# p1_bt_sorry.net
KiCad netlist of a schematic drawn in Altium Designer
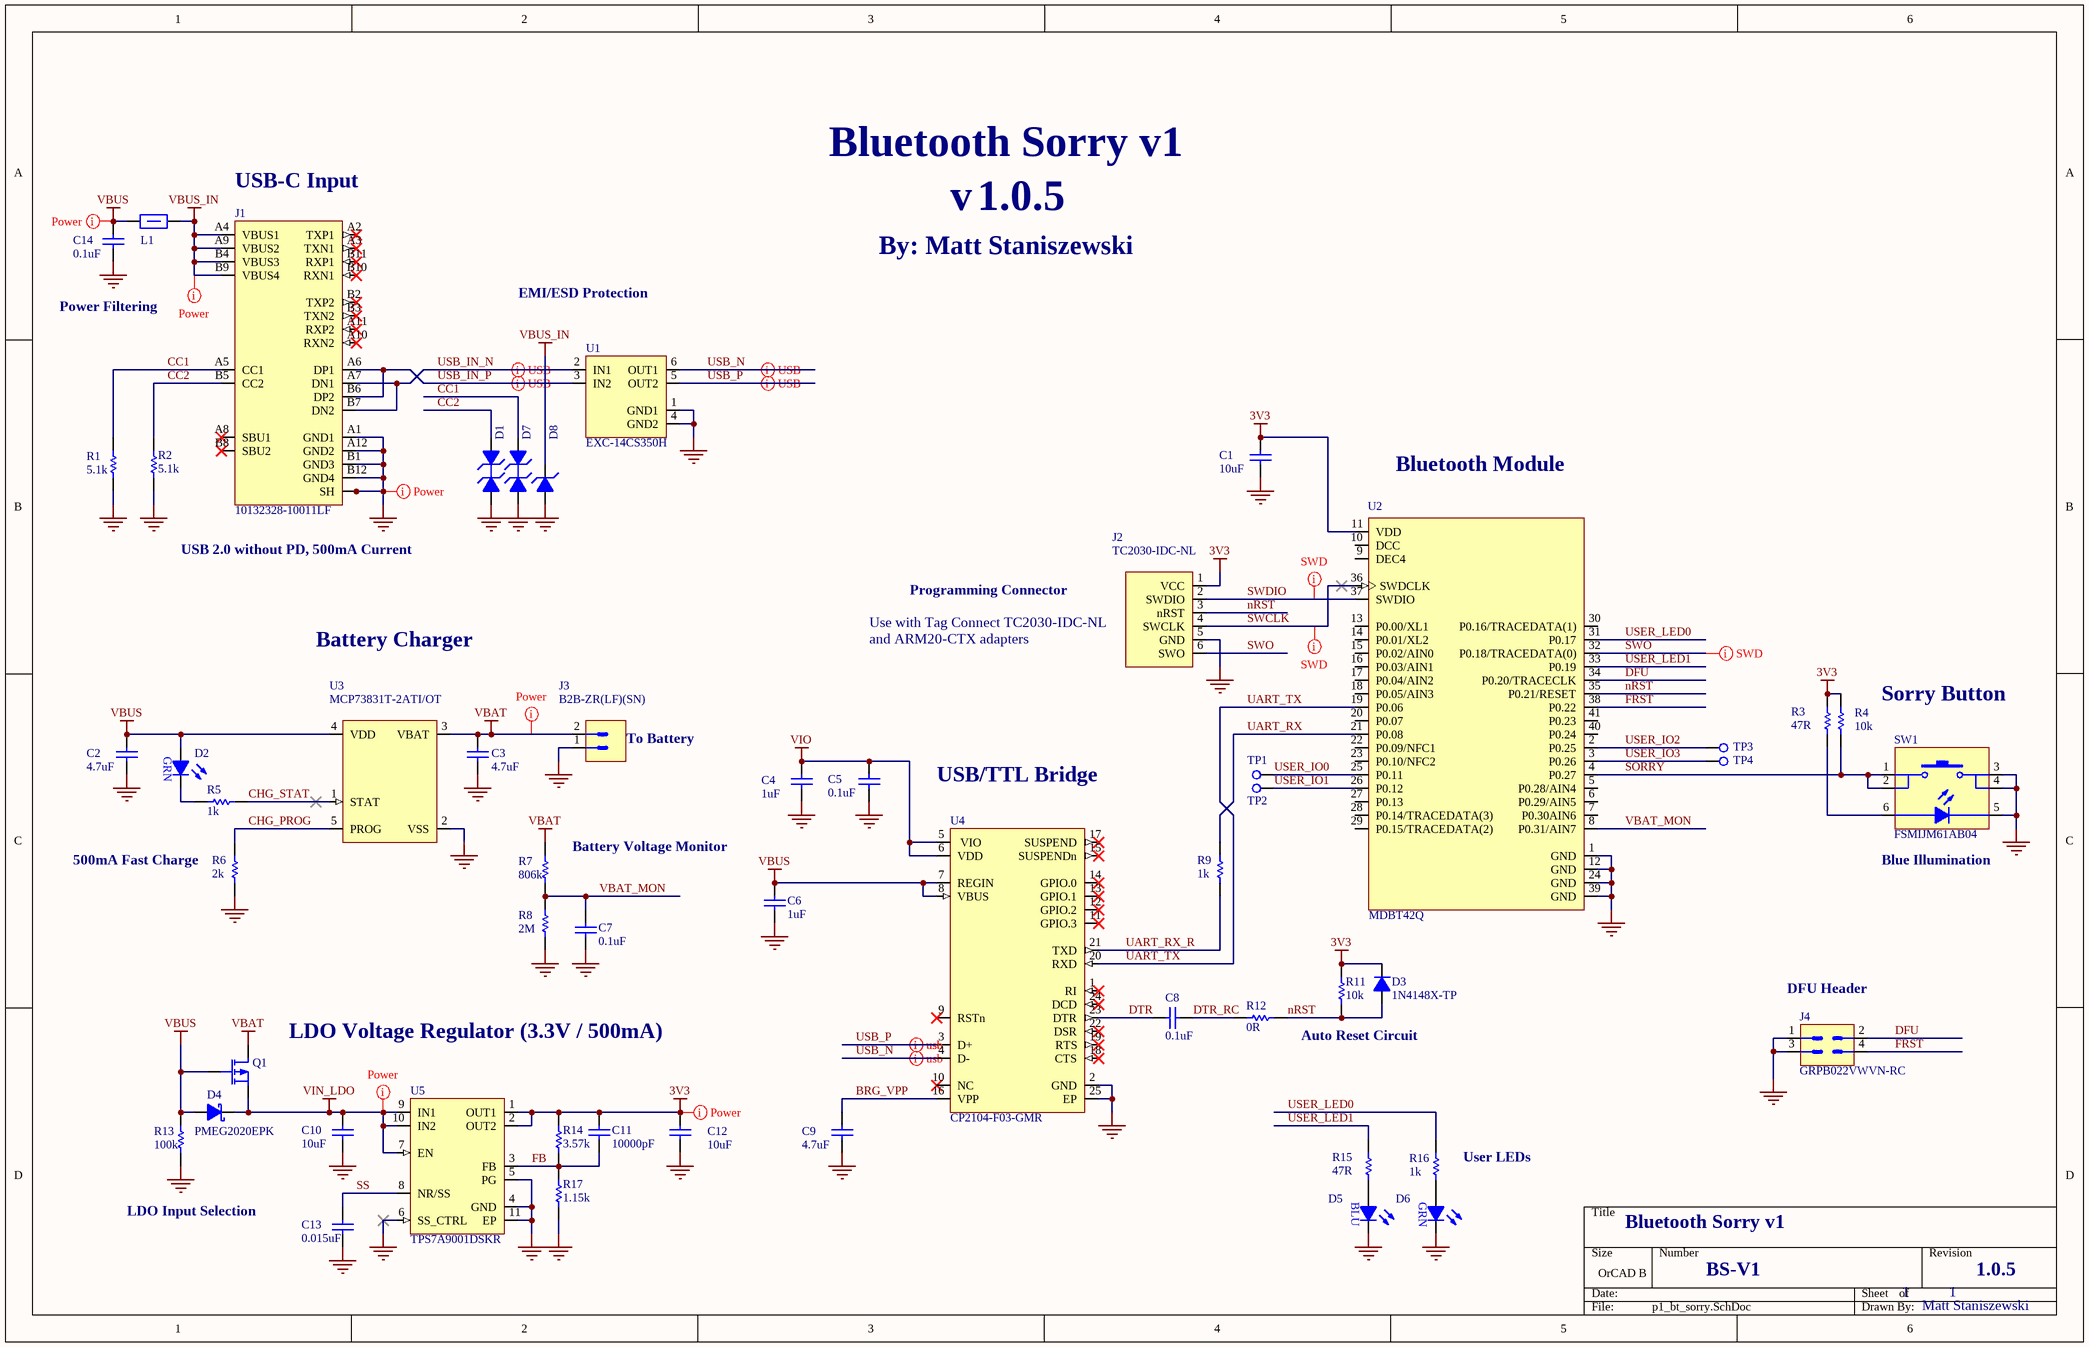
[diagram p0: p1_bt_sorry.SchDoc]

(export (version "E")
  (design (tool "Eeschema 10.0.6"))
  (components
    (comp (ref "C1")
      (value "10uF")
      (footprint "C0402")
      (description "CAP CER 10UF 10V X5R 0402")
      (fields
        (field (name "MANUFACTURER") "Samsung")
        (field (name "MANUFACTURER PART NUMBER") "CL05A106MP5NUNC")
      )
      (libsource (lib "Capacitors") (part "10uF 10V 0402"))
    )
    (comp (ref "C2")
      (value "4.7uF")
      (footprint "C0402")
      (description "CAP CER 4.7UF 16V X5R 0402")
      (fields
        (field (name "MANUFACTURER") "Samsung")
        (field (name "MANUFACTURER PART NUMBER") "CL05A475MO5NUNC")
      )
      (libsource (lib "Capacitors") (part "4.7uF 16V 0402"))
    )
    (comp (ref "C3")
      (value "4.7uF")
      (footprint "C0402")
      (description "CAP CER 4.7UF 16V X5R 0402")
      (fields
        (field (name "MANUFACTURER") "Samsung")
        (field (name "MANUFACTURER PART NUMBER") "CL05A475MO5NUNC")
      )
      (libsource (lib "Capacitors") (part "4.7uF 16V 0402"))
    )
    (comp (ref "C4")
      (value "1uF")
      (footprint "C0402")
      (description "CAP CER 1UF 25V X5R 0402")
      (fields
        (field (name "MANUFACTURER") "Taiyo Yuden")
        (field (name "MANUFACTURER PART NUMBER") "TMK105BJ105MV-F")
      )
      (libsource (lib "Capacitors") (part "1uF 25V 0402"))
    )
    (comp (ref "C5")
      (value "0.1uF")
      (footprint "C0201")
      (description "CAP CER 0.1UF 16V X5R 0201")
      (fields
        (field (name "MANUFACTURER") "Murata")
        (field (name "MANUFACTURER PART NUMBER") "GRM033R61C104ME84D")
      )
      (libsource (lib "Capacitors") (part "0.1uF 16V 0201"))
    )
    (comp (ref "C6")
      (value "1uF")
      (footprint "C0402")
      (description "CAP CER 1UF 25V X5R 0402")
      (fields
        (field (name "MANUFACTURER") "Taiyo Yuden")
        (field (name "MANUFACTURER PART NUMBER") "TMK105BJ105MV-F")
      )
      (libsource (lib "Capacitors") (part "1uF 25V 0402"))
    )
    (comp (ref "C7")
      (value "0.1uF")
      (footprint "C0201")
      (description "CAP CER 0.1UF 16V X5R 0201")
      (fields
        (field (name "MANUFACTURER") "Murata")
        (field (name "MANUFACTURER PART NUMBER") "GRM033R61C104ME84D")
      )
      (libsource (lib "Capacitors") (part "0.1uF 16V 0201"))
    )
    (comp (ref "C8")
      (value "0.1uF")
      (footprint "C0201")
      (description "CAP CER 0.1UF 16V X5R 0201")
      (fields
        (field (name "MANUFACTURER") "Murata")
        (field (name "MANUFACTURER PART NUMBER") "GRM033R61C104ME84D")
      )
      (libsource (lib "Capacitors") (part "0.1uF 16V 0201"))
    )
    (comp (ref "C9")
      (value "4.7uF")
      (footprint "C0402")
      (description "CAP CER 4.7UF 16V X5R 0402")
      (fields
        (field (name "MANUFACTURER") "Samsung")
        (field (name "MANUFACTURER PART NUMBER") "CL05A475MO5NUNC")
      )
      (libsource (lib "Capacitors") (part "4.7uF 16V 0402"))
    )
    (comp (ref "C10")
      (value "10uF")
      (footprint "C0402")
      (description "CAP CER 10UF 10V X5R 0402")
      (fields
        (field (name "MANUFACTURER") "Samsung")
        (field (name "MANUFACTURER PART NUMBER") "CL05A106MP5NUNC")
      )
      (libsource (lib "Capacitors") (part "10uF 10V 0402"))
    )
    (comp (ref "C11")
      (value "10000pF")
      (footprint "C0402")
      (description "CAP CER 10000PF 25V X7R 0402")
      (fields
        (field (name "MANUFACTURER") "Murata")
        (field (name "MANUFACTURER PART NUMBER") "GRM155R71E103KA01D")
      )
      (libsource (lib "Capacitors") (part "10000pF 25V 0402"))
    )
    (comp (ref "C12")
      (value "10uF")
      (footprint "C0402")
      (description "CAP CER 10UF 10V X5R 0402")
      (fields
        (field (name "MANUFACTURER") "Samsung")
        (field (name "MANUFACTURER PART NUMBER") "CL05A106MP5NUNC")
      )
      (libsource (lib "Capacitors") (part "10uF 10V 0402"))
    )
    (comp (ref "C13")
      (value "0.015uF")
      (footprint "C0402")
      (description "CAP CER 0.015UF 16V X7R 0402")
      (fields
        (field (name "MANUFACTURER") "Murata")
        (field (name "MANUFACTURER PART NUMBER") "GRM155R71C153KA01J")
      )
      (libsource (lib "Capacitors") (part "0.015uF 16V 0402"))
    )
    (comp (ref "C14")
      (value "0.1uF")
      (footprint "C0201")
      (description "CAP CER 0.1UF 16V X5R 0201")
      (fields
        (field (name "MANUFACTURER") "Murata")
        (field (name "MANUFACTURER PART NUMBER") "GRM033R61C104ME84D")
      )
      (libsource (lib "Capacitors") (part "0.1uF 16V 0201"))
    )
    (comp (ref "D1")
      (value "ESDAXLC6-1BU2")
      (footprint "ONS_0201")
      (description "TVS DIODE 3V 17V ST0201")
      (fields (field (name "MANUFACTURER") "STMicroelectronics"))
      (libsource (lib "Diodes") (part "ESDAXLC6-1BU2"))
    )
    (comp (ref "D2")
      (value "5988070107F")
      (footprint "LED0603")
      (description "LED GREEN CLEAR 0603 SMD")
      (fields
        (field (name "MANUFACTURER") "Dialight")
        (field (name "MANUFACTURER PART NUMBER") "598-8070-107F")
      )
      (libsource (lib "Diodes") (part "Green 0603 LED"))
    )
    (comp (ref "D3")
      (value "1N4148X-TP")
      (footprint "MCC_SOD523")
      (description "DIODE GEN PURP 75V 150MA SOD523")
      (fields (field (name "MANUFACTURER") "MCC"))
      (libsource (lib "Diodes") (part "1N4148X-TP"))
    )
    (comp (ref "D4")
      (value "PMEG2020EPK")
      (footprint "NXP_DFN1608D-2")
      (description "DIODE SCHOTTKY 20V 2A 2DFN")
      (fields
        (field (name "MANUFACTURER") "NXP Semiconductors")
        (field (name "MANUFACTURER PART NUMBER") "PMEG2020EPK,315")
      )
      (libsource (lib "Diodes") (part "PMEG2020EPK,315"))
    )
    (comp (ref "D5")
      (value "5988091107F")
      (footprint "LED0603")
      (description "LED BLUE CLEAR 0603 SMD")
      (fields
        (field (name "MANUFACTURER") "Dialight")
        (field (name "MANUFACTURER PART NUMBER") "598-8091-107F")
      )
      (libsource (lib "Diodes") (part "Blue 0603 LED"))
    )
    (comp (ref "D6")
      (value "5988070107F")
      (footprint "LED0603")
      (description "LED GREEN CLEAR 0603 SMD")
      (fields
        (field (name "MANUFACTURER") "Dialight")
        (field (name "MANUFACTURER PART NUMBER") "598-8070-107F")
      )
      (libsource (lib "Diodes") (part "Green 0603 LED"))
    )
    (comp (ref "D7")
      (value "ESDAXLC6-1BU2")
      (footprint "ONS_0201")
      (description "TVS DIODE 3V 17V ST0201")
      (fields (field (name "MANUFACTURER") "STMicroelectronics"))
      (libsource (lib "Diodes") (part "ESDAXLC6-1BU2"))
    )
    (comp (ref "D8")
      (value "ESDA7P60-1U1M")
      (footprint "STM_1610")
      (description "TVS DIODE 5V 11.6V 1610")
      (fields (field (name "MANUFACTURER") "STMicroelectronics"))
      (libsource (lib "Diodes") (part "ESDA7P60-1U1M"))
    )
    (comp (ref "J1")
      (value "10132328-10011LF")
      (footprint "AMP_USBC_VT")
      (description "CONN RCPT USB3.1 TYPEC 24POS SMD")
      (fields (field (name "MANUFACTURER") "Amphenol FCI"))
      (libsource (lib "Connectors") (part "USB-C Vertical"))
    )
    (comp (ref "J2")
      (value "TC2030-IDC-NL")
      (footprint "TAG_6P")
      (description "TAG CONNECT 6PIN SWD")
      (fields (field (name "MANUFACTURER") "Tag Connect"))
      (libsource (lib "Connectors") (part "Tag Connect 6-Pin SWD"))
    )
    (comp (ref "J3")
      (value "B2B-ZR(LF)(SN)")
      (footprint "JST_ZH_2P_PTH_VT")
      (description "CONN HEADER ZH TOP 2POS 1.5MM")
      (fields (field (name "MANUFACTURER") "JST"))
      (libsource (lib "Connectors") (part "JST ZH 2-Pin PTH Vertical"))
    )
    (comp (ref "J4")
      (value "GRPB022VWVN-RC")
      (footprint "HDR10_2X2_0.05IN")
      (description "CONN HEADER VERT 4POS 1.27MM")
      (fields (field (name "MANUFACTURER") "Sullins"))
      (libsource (lib "Connectors") (part "4-Pin 2x2 0.05in Header"))
    )
    (comp (ref "L1")
      (value "BLM15PX601SN1D")
      (footprint "L0402")
      (description "FERRITE BEAD 600 OHM 0402 1LN")
      (fields (field (name "MANUFACTURER") "Murata") (field (name "TOLERANCE") "25%"))
      (libsource (lib "Inductors") (part "BLM15PX601SN1D"))
    )
    (comp (ref "Q1")
      (value "DMP21D0UFB4-7B")
      (footprint "DIO_X2-DFN1006-3")
      (description "MOSFET P-CH 20V 770MA 3DFN")
      (fields (field (name "MANUFACTURER") "Diodes"))
      (libsource (lib "ICs") (part "DMP21D0UFB4-7B"))
    )
    (comp (ref "R1")
      (value "5.1k")
      (footprint "R0402")
      (description "RES SMD 5.1K OHM 1% 1/16W 0402")
      (fields
        (field (name "MANUFACTURER") "Yageo")
        (field (name "MANUFACTURER PART NUMBER") "RC0402FR-075K1L")
      )
      (libsource (lib "Resistors") (part "5.1k 0402"))
    )
    (comp (ref "R2")
      (value "5.1k")
      (footprint "R0402")
      (description "RES SMD 5.1K OHM 1% 1/16W 0402")
      (fields
        (field (name "MANUFACTURER") "Yageo")
        (field (name "MANUFACTURER PART NUMBER") "RC0402FR-075K1L")
      )
      (libsource (lib "Resistors") (part "5.1k 0402"))
    )
    (comp (ref "R3")
      (value "47R")
      (footprint "R0402")
      (description "RES SMD 47 OHM 1% 1/16W 0402")
      (fields
        (field (name "MANUFACTURER") "Yageo")
        (field (name "MANUFACTURER PART NUMBER") "RC0402FR-0747RL")
      )
      (libsource (lib "Resistors") (part "47R 0402"))
    )
    (comp (ref "R4")
      (value "10k")
      (footprint "R0402")
      (description "RES SMD 10K OHM 1% 1/16W 0402")
      (fields
        (field (name "MANUFACTURER") "Yageo Phycomp")
        (field (name "MANUFACTURER PART NUMBER") "RC0402FR-0710KL")
      )
      (libsource (lib "Resistors") (part "10k 0402"))
    )
    (comp (ref "R5")
      (value "1k")
      (footprint "R0402")
      (description "RES SMD 1K OHM 1% 1/16W 0402")
      (fields
        (field (name "MANUFACTURER") "Yageo")
        (field (name "MANUFACTURER PART NUMBER") "RC0402FR-071KL")
      )
      (libsource (lib "Resistors") (part "1k 0402"))
    )
    (comp (ref "R6")
      (value "2k")
      (footprint "R0402")
      (description "RES SMD 2K OHM 1% 1/16W 0402")
      (fields
        (field (name "MANUFACTURER") "Yageo")
        (field (name "MANUFACTURER PART NUMBER") "RC0402FR-072KL")
      )
      (libsource (lib "Resistors") (part "2k 0402"))
    )
    (comp (ref "R7")
      (value "806k")
      (footprint "R0402")
      (description "RES SMD 806K OHM 1% 1/10W 0402")
      (fields
        (field (name "MANUFACTURER") "Panasonic")
        (field (name "MANUFACTURER PART NUMBER") "ERJ-2RKF8063X")
      )
      (libsource (lib "Resistors") (part "806k 0402"))
    )
    (comp (ref "R8")
      (value "2M")
      (footprint "R0402")
      (description "RES SMD 2M OHM 1% 1/16W 0402")
      (fields
        (field (name "MANUFACTURER") "Samsung")
        (field (name "MANUFACTURER PART NUMBER") "RC1005F205CS")
      )
      (libsource (lib "Resistors") (part "2M 0402"))
    )
    (comp (ref "R9")
      (value "1k")
      (footprint "R0402")
      (description "RES SMD 1K OHM 1% 1/16W 0402")
      (fields
        (field (name "MANUFACTURER") "Yageo")
        (field (name "MANUFACTURER PART NUMBER") "RC0402FR-071KL")
      )
      (libsource (lib "Resistors") (part "1k 0402"))
    )
    (comp (ref "R11")
      (value "10k")
      (footprint "R0402")
      (description "RES SMD 10K OHM 1% 1/16W 0402")
      (fields
        (field (name "MANUFACTURER") "Yageo Phycomp")
        (field (name "MANUFACTURER PART NUMBER") "RC0402FR-0710KL")
      )
      (libsource (lib "Resistors") (part "10k 0402"))
    )
    (comp (ref "R12")
      (value "0R")
      (footprint "R0402")
      (description "RES SMD 0 OHM JUMPER 1/16W 0402")
      (fields
        (field (name "MANUFACTURER") "Yageo")
        (field (name "MANUFACTURER PART NUMBER") "RC0402FR-070RL")
      )
      (libsource (lib "Resistors") (part "0R 0402"))
    )
    (comp (ref "R13")
      (value "100k")
      (footprint "R0402")
      (description "RES SMD 100K OHM 1% 1/16W 0402")
      (fields
        (field (name "MANUFACTURER") "Yageo")
        (field (name "MANUFACTURER PART NUMBER") "RC0402FR-07100KL")
      )
      (libsource (lib "Resistors") (part "100k 0402"))
    )
    (comp (ref "R14")
      (value "3.57k")
      (footprint "R0402")
      (description "RES SMD 3.57K OHM 1% 1/10W 0402")
      (fields
        (field (name "MANUFACTURER") "Panasonic")
        (field (name "MANUFACTURER PART NUMBER") "ERJ-2RKF3571X")
      )
      (libsource (lib "Resistors") (part "3.57k 0402"))
    )
    (comp (ref "R15")
      (value "47R")
      (footprint "R0402")
      (description "RES SMD 47 OHM 1% 1/16W 0402")
      (fields
        (field (name "MANUFACTURER") "Yageo")
        (field (name "MANUFACTURER PART NUMBER") "RC0402FR-0747RL")
      )
      (libsource (lib "Resistors") (part "47R 0402"))
    )
    (comp (ref "R16")
      (value "1k")
      (footprint "R0402")
      (description "RES SMD 1K OHM 1% 1/16W 0402")
      (fields
        (field (name "MANUFACTURER") "Yageo")
        (field (name "MANUFACTURER PART NUMBER") "RC0402FR-071KL")
      )
      (libsource (lib "Resistors") (part "1k 0402"))
    )
    (comp (ref "R17")
      (value "1.15k")
      (footprint "R0402")
      (description "RES SMD 1.15K OHM 1% 1/10W 0402")
      (fields
        (field (name "MANUFACTURER") "Panasonic")
        (field (name "MANUFACTURER PART NUMBER") "ERJ-2RKF1151X")
      )
      (libsource (lib "Resistors") (part "1.15k 0402"))
    )
    (comp (ref "SW1")
      (value "FSMIJM61AB04")
      (footprint "TE_FSMIJM61AB04")
      (description "SWITCH TACTILE SPST-NO 50MA 12V")
      (fields (field (name "MANUFACTURER") "TE Connectivity Alcoswitch"))
      (libsource (lib "Misc") (part "Pushbutton Switch, Blue Illuminated"))
    )
    (comp (ref "TP1")
      (value "TP SMT 0.5MM")
      (footprint "TP_SMT_0.5MM")
      (description "0.5mm SMT Test Point")
      (libsource (lib "Misc") (part "TP SMT 0.5MM"))
    )
    (comp (ref "TP2")
      (value "TP SMT 0.5MM")
      (footprint "TP_SMT_0.5MM")
      (description "0.5mm SMT Test Point")
      (libsource (lib "Misc") (part "TP SMT 0.5MM"))
    )
    (comp (ref "TP3")
      (value "TP SMT 0.5MM")
      (footprint "TP_SMT_0.5MM")
      (description "0.5mm SMT Test Point")
      (libsource (lib "Misc") (part "TP SMT 0.5MM"))
    )
    (comp (ref "TP4")
      (value "TP SMT 0.5MM")
      (footprint "TP_SMT_0.5MM")
      (description "0.5mm SMT Test Point")
      (libsource (lib "Misc") (part "TP SMT 0.5MM"))
    )
    (comp (ref "U1")
      (value "EXC-14CS350H")
      (footprint "PAN_EXC14CS")
      (description "CMC 100MA 2LN 35 OHM SMD ESD")
      (fields (field (name "MANUFACTURER") "Panasonic"))
      (libsource (lib "ICs") (part "EXC-14CS350H"))
    )
    (comp (ref "U2")
      (value "MDBT42Q")
      (footprint "RAY_MDBT42Q")
      (description "MDBT42Q NRF52832 BASED BLE MODUL")
      (fields
        (field (name "MANUFACTURER") "Seeed Studio")
        (field (name "MANUFACTURER PART NUMBER") "317030213")
      )
      (libsource (lib "ICs") (part "MDBT42Q"))
    )
    (comp (ref "U3")
      (value "MCP73831T-2ATI/OT")
      (footprint "MCP_SOT23-5")
      (description "IC CONTROLLR LI-ION 4.2V SOT23-5")
      (fields (field (name "MANUFACTURER") "Microchip"))
      (libsource (lib "ICs") (part "MCP73831T-2ATI/OT"))
    )
    (comp (ref "U4")
      (value "CP2104-F03-GMR")
      (footprint "SIL_QFN-24")
      (description "IC SGL USB-TO-UART BRIDGE 24QFN")
      (fields (field (name "MANUFACTURER") "Silicon Labs"))
      (libsource (lib "ICs") (part "CP2104-F03-GMR"))
    )
    (comp (ref "U5")
      (value "TPS7A9001DSKR")
      (footprint "TI_DSK")
      (description "ULTRA LOW NOISE 0.5A LDO WITH P")
      (fields (field (name "MANUFACTURER") "Texas Instruments"))
      (libsource (lib "ICs") (part "TPS7A9001DSKR"))
    )
  )
  (nets
    (net (code "1") (name "/BRG_VPP") (class "Default")
      (node (ref "C9") (pin "2") (pinfunction "2_2") (pintype "passive"))
      (node (ref "U4") (pin "16") (pinfunction "VPP_16") (pintype "power_in"))
    )
    (net (code "2") (name "/CC1") (class "Default")
      (node (ref "D7") (pin "2") (pinfunction "A2_2") (pintype "passive"))
      (node (ref "J1") (pin "A5") (pinfunction "CC1_A5") (pintype "passive"))
      (node (ref "R1") (pin "2") (pinfunction "2_2") (pintype "passive"))
    )
    (net (code "3") (name "/CC2") (class "Default")
      (node (ref "D1") (pin "2") (pinfunction "A2_2") (pintype "passive"))
      (node (ref "J1") (pin "B5") (pinfunction "CC2_B5") (pintype "passive"))
      (node (ref "R2") (pin "2") (pinfunction "2_2") (pintype "passive"))
    )
    (net (code "4") (name "/CHG_PROG") (class "Default")
      (node (ref "R6") (pin "2") (pinfunction "2_2") (pintype "passive"))
      (node (ref "U3") (pin "5") (pinfunction "PROG_5") (pintype "passive"))
    )
    (net (code "5") (name "/CHG_STAT") (class "Default")
      (node (ref "R5") (pin "2") (pinfunction "2_2") (pintype "passive"))
      (node (ref "U3") (pin "1") (pinfunction "STAT_1") (pintype "input"))
    )
    (net (code "6") (name "/DFU") (class "Default")
      (node (ref "J4") (pin "2") (pinfunction "2_2") (pintype "passive"))
      (node (ref "U2") (pin "34") (pinfunction "P0.20/TRACECLK_34") (pintype "bidirectional"))
    )
    (net (code "7") (name "/DTR") (class "Default")
      (node (ref "C8") (pin "2") (pinfunction "2_2") (pintype "passive"))
      (node (ref "U4") (pin "23") (pinfunction "DTR_23") (pintype "output"))
    )
    (net (code "8") (name "/DTR_RC") (class "Default")
      (node (ref "C8") (pin "1") (pinfunction "1_1") (pintype "passive"))
      (node (ref "R12") (pin "1") (pinfunction "1_1") (pintype "passive"))
    )
    (net (code "9") (name "/FB") (class "Default")
      (node (ref "C11") (pin "1") (pinfunction "1_1") (pintype "passive"))
      (node (ref "R14") (pin "1") (pinfunction "1_1") (pintype "passive"))
      (node (ref "R17") (pin "2") (pinfunction "2_2") (pintype "passive"))
      (node (ref "U5") (pin "3") (pinfunction "FB_3") (pintype "passive"))
    )
    (net (code "10") (name "/FRST") (class "Default")
      (node (ref "J4") (pin "4") (pinfunction "4_4") (pintype "passive"))
      (node (ref "U2") (pin "38") (pinfunction "P0.22_38") (pintype "bidirectional"))
    )
    (net (code "11") (name "/SORRY") (class "Default")
      (node (ref "R4") (pin "1") (pinfunction "1_1") (pintype "passive"))
      (node (ref "SW1") (pin "1") (pinfunction "1_1") (pintype "passive"))
      (node (ref "SW1") (pin "2") (pinfunction "2_2") (pintype "passive"))
      (node (ref "U2") (pin "4") (pinfunction "P0.27_4") (pintype "bidirectional"))
    )
    (net (code "12") (name "/SS") (class "Default")
      (node (ref "C13") (pin "2") (pinfunction "2_2") (pintype "passive"))
      (node (ref "U5") (pin "8") (pinfunction "NR/SS_8") (pintype "passive"))
    )
    (net (code "13") (name "/SWCLK") (class "Default")
      (node (ref "J2") (pin "4") (pinfunction "SWCLK_4") (pintype "passive"))
      (node (ref "U2") (pin "36") (pinfunction "SWDCLK_36") (pintype "input"))
    )
    (net (code "14") (name "/SWDIO") (class "Default")
      (node (ref "J2") (pin "2") (pinfunction "SWDIO_2") (pintype "passive"))
      (node (ref "U2") (pin "37") (pinfunction "SWDIO_37") (pintype "bidirectional"))
    )
    (net (code "15") (name "/SWO") (class "Default")
      (node (ref "J2") (pin "6") (pinfunction "SWO_6") (pintype "passive"))
      (node (ref "U2") (pin "32") (pinfunction "P0.18/TRACEDATA(0)_32") (pintype "bidirectional"))
    )
    (net (code "16") (name "/UART_RX") (class "Default")
      (node (ref "R9") (pin "1") (pinfunction "1_1") (pintype "passive"))
      (node (ref "U2") (pin "21") (pinfunction "P0.08_21") (pintype "bidirectional"))
    )
    (net (code "17") (name "/UART_RX_R") (class "Default")
      (node (ref "R9") (pin "2") (pinfunction "2_2") (pintype "passive"))
      (node (ref "U4") (pin "21") (pinfunction "TXD_21") (pintype "output"))
    )
    (net (code "18") (name "/UART_TX") (class "Default")
      (node (ref "U2") (pin "19") (pinfunction "P0.06_19") (pintype "bidirectional"))
      (node (ref "U4") (pin "20") (pinfunction "RXD_20") (pintype "input"))
    )
    (net (code "19") (name "/USB_IN_N") (class "Default")
      (node (ref "J1") (pin "A7") (pinfunction "DN1_A7") (pintype "bidirectional"))
      (node (ref "J1") (pin "B7") (pinfunction "DN2_B7") (pintype "bidirectional"))
      (node (ref "U1") (pin "2") (pinfunction "IN1_2") (pintype "bidirectional"))
    )
    (net (code "20") (name "/USB_IN_P") (class "Default")
      (node (ref "J1") (pin "A6") (pinfunction "DP1_A6") (pintype "bidirectional"))
      (node (ref "J1") (pin "B6") (pinfunction "DP2_B6") (pintype "bidirectional"))
      (node (ref "U1") (pin "3") (pinfunction "IN2_3") (pintype "bidirectional"))
    )
    (net (code "21") (name "/USB_N") (class "Default")
      (node (ref "U1") (pin "6") (pinfunction "OUT1_6") (pintype "bidirectional"))
      (node (ref "U4") (pin "4") (pinfunction "D-_4") (pintype "bidirectional"))
    )
    (net (code "22") (name "/USB_P") (class "Default")
      (node (ref "U1") (pin "5") (pinfunction "OUT2_5") (pintype "bidirectional"))
      (node (ref "U4") (pin "3") (pinfunction "D+_3") (pintype "bidirectional"))
    )
    (net (code "23") (name "/USER_IO0") (class "Default")
      (node (ref "TP1") (pin "1") (pinfunction "1_1") (pintype "passive"))
      (node (ref "U2") (pin "25") (pinfunction "P0.11_25") (pintype "bidirectional"))
    )
    (net (code "24") (name "/USER_IO1") (class "Default")
      (node (ref "TP2") (pin "1") (pinfunction "1_1") (pintype "passive"))
      (node (ref "U2") (pin "26") (pinfunction "P0.12_26") (pintype "bidirectional"))
    )
    (net (code "25") (name "/USER_IO2") (class "Default")
      (node (ref "TP3") (pin "1") (pinfunction "1_1") (pintype "passive"))
      (node (ref "U2") (pin "2") (pinfunction "P0.25_2") (pintype "bidirectional"))
    )
    (net (code "26") (name "/USER_IO3") (class "Default")
      (node (ref "TP4") (pin "1") (pinfunction "1_1") (pintype "passive"))
      (node (ref "U2") (pin "3") (pinfunction "P0.26_3") (pintype "bidirectional"))
    )
    (net (code "27") (name "/USER_LED0") (class "Default")
      (node (ref "R16") (pin "2") (pinfunction "2_2") (pintype "passive"))
      (node (ref "U2") (pin "31") (pinfunction "P0.17_31") (pintype "bidirectional"))
    )
    (net (code "28") (name "/USER_LED1") (class "Default")
      (node (ref "R15") (pin "2") (pinfunction "2_2") (pintype "passive"))
      (node (ref "U2") (pin "33") (pinfunction "P0.19_33") (pintype "bidirectional"))
    )
    (net (code "29") (name "/VBAT_MON") (class "Default")
      (node (ref "C7") (pin "2") (pinfunction "2_2") (pintype "passive"))
      (node (ref "R7") (pin "1") (pinfunction "1_1") (pintype "passive"))
      (node (ref "R8") (pin "2") (pinfunction "2_2") (pintype "passive"))
      (node (ref "U2") (pin "8") (pinfunction "P0.31/AIN7_8") (pintype "bidirectional"))
    )
    (net (code "30") (name "/nRST") (class "Default")
      (node (ref "D3") (pin "2") (pinfunction "A_2") (pintype "passive"))
      (node (ref "J2") (pin "3") (pinfunction "nRST_3") (pintype "passive"))
      (node (ref "R11") (pin "1") (pinfunction "1_1") (pintype "passive"))
      (node (ref "R12") (pin "2") (pinfunction "2_2") (pintype "passive"))
      (node (ref "U2") (pin "35") (pinfunction "P0.21/RESET_35") (pintype "bidirectional"))
    )
    (net (code "31") (name "3V3") (class "Default")
      (node (ref "C1") (pin "2") (pinfunction "2_2") (pintype "passive"))
      (node (ref "C11") (pin "2") (pinfunction "2_2") (pintype "passive"))
      (node (ref "C12") (pin "2") (pinfunction "2_2") (pintype "passive"))
      (node (ref "D3") (pin "1") (pinfunction "K_1") (pintype "passive"))
      (node (ref "J2") (pin "1") (pinfunction "VCC_1") (pintype "passive"))
      (node (ref "R11") (pin "2") (pinfunction "2_2") (pintype "passive"))
      (node (ref "R14") (pin "2") (pinfunction "2_2") (pintype "passive"))
      (node (ref "R3") (pin "2") (pinfunction "2_2") (pintype "passive"))
      (node (ref "R4") (pin "2") (pinfunction "2_2") (pintype "passive"))
      (node (ref "U2") (pin "11") (pinfunction "VDD_11") (pintype "power_in"))
      (node (ref "U5") (pin "1") (pinfunction "OUT1_1") (pintype "power_in"))
      (node (ref "U5") (pin "2") (pinfunction "OUT2_2") (pintype "power_in"))
    )
    (net (code "32") (name "GND") (class "Default")
      (node (ref "C1") (pin "1") (pinfunction "1_1") (pintype "passive"))
      (node (ref "C10") (pin "1") (pinfunction "1_1") (pintype "passive"))
      (node (ref "C12") (pin "1") (pinfunction "1_1") (pintype "passive"))
      (node (ref "C13") (pin "1") (pinfunction "1_1") (pintype "passive"))
      (node (ref "C14") (pin "1") (pinfunction "1_1") (pintype "passive"))
      (node (ref "C2") (pin "1") (pinfunction "1_1") (pintype "passive"))
      (node (ref "C3") (pin "1") (pinfunction "1_1") (pintype "passive"))
      (node (ref "C4") (pin "1") (pinfunction "1_1") (pintype "passive"))
      (node (ref "C5") (pin "1") (pinfunction "1_1") (pintype "passive"))
      (node (ref "C6") (pin "1") (pinfunction "1_1") (pintype "passive"))
      (node (ref "C7") (pin "1") (pinfunction "1_1") (pintype "passive"))
      (node (ref "C9") (pin "1") (pinfunction "1_1") (pintype "passive"))
      (node (ref "D1") (pin "1") (pinfunction "A1_1") (pintype "passive"))
      (node (ref "D5") (pin "1") (pinfunction "K_1") (pintype "passive"))
      (node (ref "D6") (pin "1") (pinfunction "K_1") (pintype "passive"))
      (node (ref "D7") (pin "1") (pinfunction "A1_1") (pintype "passive"))
      (node (ref "D8") (pin "2") (pinfunction "A_2") (pintype "passive"))
      (node (ref "J1") (pin "A1") (pinfunction "GND1_A1") (pintype "power_in"))
      (node (ref "J1") (pin "A12") (pinfunction "GND2_A12") (pintype "power_in"))
      (node (ref "J1") (pin "B1") (pinfunction "GND3_B1") (pintype "power_in"))
      (node (ref "J1") (pin "B12") (pinfunction "GND4_B12") (pintype "power_in"))
      (node (ref "J1") (pin "SHA1") (pinfunction "SH_SHA1") (pintype "passive"))
      (node (ref "J1") (pin "SHA2") (pinfunction "SH_SHA2") (pintype "passive"))
      (node (ref "J1") (pin "SHA3") (pinfunction "SH_SHA3") (pintype "passive"))
      (node (ref "J1") (pin "SHA4") (pinfunction "SH_SHA4") (pintype "passive"))
      (node (ref "J1") (pin "SHA5") (pinfunction "SH_SHA5") (pintype "passive"))
      (node (ref "J1") (pin "SHA6") (pinfunction "SH_SHA6") (pintype "passive"))
      (node (ref "J1") (pin "SHA7") (pinfunction "SH_SHA7") (pintype "passive"))
      (node (ref "J1") (pin "SHB1") (pinfunction "SH_SHB1") (pintype "passive"))
      (node (ref "J1") (pin "SHB2") (pinfunction "SH_SHB2") (pintype "passive"))
      (node (ref "J1") (pin "SHB3") (pinfunction "SH_SHB3") (pintype "passive"))
      (node (ref "J1") (pin "SHB4") (pinfunction "SH_SHB4") (pintype "passive"))
      (node (ref "J1") (pin "SHB5") (pinfunction "SH_SHB5") (pintype "passive"))
      (node (ref "J1") (pin "SHB6") (pinfunction "SH_SHB6") (pintype "passive"))
      (node (ref "J1") (pin "SHB7") (pinfunction "SH_SHB7") (pintype "passive"))
      (node (ref "J2") (pin "5") (pinfunction "GND_5") (pintype "passive"))
      (node (ref "J3") (pin "1") (pinfunction "1_1") (pintype "passive"))
      (node (ref "J4") (pin "1") (pinfunction "1_1") (pintype "passive"))
      (node (ref "J4") (pin "3") (pinfunction "3_3") (pintype "passive"))
      (node (ref "R1") (pin "1") (pinfunction "1_1") (pintype "passive"))
      (node (ref "R13") (pin "1") (pinfunction "1_1") (pintype "passive"))
      (node (ref "R17") (pin "1") (pinfunction "1_1") (pintype "passive"))
      (node (ref "R2") (pin "1") (pinfunction "1_1") (pintype "passive"))
      (node (ref "R6") (pin "1") (pinfunction "1_1") (pintype "passive"))
      (node (ref "R8") (pin "1") (pinfunction "1_1") (pintype "passive"))
      (node (ref "SW1") (pin "3") (pinfunction "3_3") (pintype "passive"))
      (node (ref "SW1") (pin "4") (pinfunction "4_4") (pintype "passive"))
      (node (ref "SW1") (pin "5") (pinfunction "5_5") (pintype "passive"))
      (node (ref "U1") (pin "1") (pinfunction "GND1_1") (pintype "power_in"))
      (node (ref "U1") (pin "4") (pinfunction "GND2_4") (pintype "power_in"))
      (node (ref "U2") (pin "1") (pinfunction "GND_1") (pintype "power_in"))
      (node (ref "U2") (pin "12") (pinfunction "GND_12") (pintype "power_in"))
      (node (ref "U2") (pin "24") (pinfunction "GND_24") (pintype "power_in"))
      (node (ref "U2") (pin "39") (pinfunction "GND_39") (pintype "power_in"))
      (node (ref "U3") (pin "2") (pinfunction "VSS_2") (pintype "power_in"))
      (node (ref "U4") (pin "2") (pinfunction "GND_2") (pintype "power_in"))
      (node (ref "U4") (pin "25") (pinfunction "EP_25") (pintype "power_in"))
      (node (ref "U5") (pin "11") (pinfunction "EP_11") (pintype "power_in"))
      (node (ref "U5") (pin "4") (pinfunction "GND_4") (pintype "power_in"))
      (node (ref "U5") (pin "5") (pinfunction "PG_5") (pintype "open_collector"))
      (node (ref "U5") (pin "6") (pinfunction "SS_CTRL_6") (pintype "input"))
    )
    (net (code "33") (name "Net-(D2-K)") (class "Default")
      (node (ref "D2") (pin "1") (pinfunction "K_1") (pintype "passive"))
      (node (ref "R5") (pin "1") (pinfunction "1_1") (pintype "passive"))
    )
    (net (code "34") (name "Net-(D5-A)") (class "Default")
      (node (ref "D5") (pin "2") (pinfunction "A_2") (pintype "passive"))
      (node (ref "R15") (pin "1") (pinfunction "1_1") (pintype "passive"))
    )
    (net (code "35") (name "Net-(D6-A)") (class "Default")
      (node (ref "D6") (pin "2") (pinfunction "A_2") (pintype "passive"))
      (node (ref "R16") (pin "1") (pinfunction "1_1") (pintype "passive"))
    )
    (net (code "36") (name "Net-(R3-Pad1)") (class "Default")
      (node (ref "R3") (pin "1") (pinfunction "1_1") (pintype "passive"))
      (node (ref "SW1") (pin "6") (pinfunction "6_6") (pintype "passive"))
    )
    (net (code "37") (name "VBAT") (class "Default")
      (node (ref "C3") (pin "2") (pinfunction "2_2") (pintype "passive"))
      (node (ref "J3") (pin "2") (pinfunction "2_2") (pintype "passive"))
      (node (ref "Q1") (pin "3") (pinfunction "D_3") (pintype "passive"))
      (node (ref "R7") (pin "2") (pinfunction "2_2") (pintype "passive"))
      (node (ref "U3") (pin "3") (pinfunction "VBAT_3") (pintype "power_in"))
    )
    (net (code "38") (name "VBUS") (class "Default")
      (node (ref "C14") (pin "2") (pinfunction "2_2") (pintype "passive"))
      (node (ref "C2") (pin "2") (pinfunction "2_2") (pintype "passive"))
      (node (ref "C6") (pin "2") (pinfunction "2_2") (pintype "passive"))
      (node (ref "D2") (pin "2") (pinfunction "A_2") (pintype "passive"))
      (node (ref "D4") (pin "2") (pinfunction "A_2") (pintype "passive"))
      (node (ref "L1") (pin "2") (pinfunction "2_2") (pintype "passive"))
      (node (ref "Q1") (pin "1") (pinfunction "G_1") (pintype "passive"))
      (node (ref "R13") (pin "2") (pinfunction "2_2") (pintype "passive"))
      (node (ref "U3") (pin "4") (pinfunction "VDD_4") (pintype "power_in"))
      (node (ref "U4") (pin "7") (pinfunction "REGIN_7") (pintype "power_in"))
      (node (ref "U4") (pin "8") (pinfunction "VBUS_8") (pintype "input"))
    )
    (net (code "39") (name "VBUS_IN") (class "Default")
      (node (ref "D8") (pin "1") (pinfunction "K_1") (pintype "passive"))
      (node (ref "J1") (pin "A4") (pinfunction "VBUS1_A4") (pintype "power_in"))
      (node (ref "J1") (pin "A9") (pinfunction "VBUS2_A9") (pintype "power_in"))
      (node (ref "J1") (pin "B4") (pinfunction "VBUS3_B4") (pintype "power_in"))
      (node (ref "J1") (pin "B9") (pinfunction "VBUS4_B9") (pintype "power_in"))
      (node (ref "L1") (pin "1") (pinfunction "1_1") (pintype "passive"))
    )
    (net (code "40") (name "VIN_LDO") (class "Default")
      (node (ref "C10") (pin "2") (pinfunction "2_2") (pintype "passive"))
      (node (ref "D4") (pin "1") (pinfunction "K_1") (pintype "passive"))
      (node (ref "Q1") (pin "2") (pinfunction "S_2") (pintype "passive"))
      (node (ref "U5") (pin "10") (pinfunction "IN2_10") (pintype "power_in"))
      (node (ref "U5") (pin "7") (pinfunction "EN_7") (pintype "input"))
      (node (ref "U5") (pin "9") (pinfunction "IN1_9") (pintype "power_in"))
    )
    (net (code "41") (name "VIO") (class "Default")
      (node (ref "C4") (pin "2") (pinfunction "2_2") (pintype "passive"))
      (node (ref "C5") (pin "2") (pinfunction "2_2") (pintype "passive"))
      (node (ref "U4") (pin "5") (pinfunction "_VIO_5") (pintype "power_in"))
      (node (ref "U4") (pin "6") (pinfunction "VDD_6") (pintype "power_in"))
    )
    (net (code "42") (name "unconnected-(J1-RXN1-PadB10)") (class "Default")
      (node (ref "J1") (pin "B10") (pinfunction "RXN1_B10") (pintype "input+no_connect"))
    )
    (net (code "43") (name "unconnected-(J1-RXN2-PadA10)") (class "Default")
      (node (ref "J1") (pin "A10") (pinfunction "RXN2_A10") (pintype "input+no_connect"))
    )
    (net (code "44") (name "unconnected-(J1-RXP1-PadB11)") (class "Default")
      (node (ref "J1") (pin "B11") (pinfunction "RXP1_B11") (pintype "input+no_connect"))
    )
    (net (code "45") (name "unconnected-(J1-RXP2-PadA11)") (class "Default")
      (node (ref "J1") (pin "A11") (pinfunction "RXP2_A11") (pintype "input+no_connect"))
    )
    (net (code "46") (name "unconnected-(J1-SBU1-PadA8)") (class "Default")
      (node (ref "J1") (pin "A8") (pinfunction "SBU1_A8") (pintype "passive+no_connect"))
    )
    (net (code "47") (name "unconnected-(J1-SBU2-PadB8)") (class "Default")
      (node (ref "J1") (pin "B8") (pinfunction "SBU2_B8") (pintype "passive+no_connect"))
    )
    (net (code "48") (name "unconnected-(J1-TXN1-PadA3)") (class "Default")
      (node (ref "J1") (pin "A3") (pinfunction "TXN1_A3") (pintype "output+no_connect"))
    )
    (net (code "49") (name "unconnected-(J1-TXN2-PadB3)") (class "Default")
      (node (ref "J1") (pin "B3") (pinfunction "TXN2_B3") (pintype "output+no_connect"))
    )
    (net (code "50") (name "unconnected-(J1-TXP1-PadA2)") (class "Default")
      (node (ref "J1") (pin "A2") (pinfunction "TXP1_A2") (pintype "output+no_connect"))
    )
    (net (code "51") (name "unconnected-(J1-TXP2-PadB2)") (class "Default")
      (node (ref "J1") (pin "B2") (pinfunction "TXP2_B2") (pintype "output+no_connect"))
    )
    (net (code "52") (name "unconnected-(U2-DCC-Pad10)") (class "Default")
      (node (ref "U2") (pin "10") (pinfunction "DCC_10") (pintype "power_in"))
    )
    (net (code "53") (name "unconnected-(U2-DEC4-Pad9)") (class "Default")
      (node (ref "U2") (pin "9") (pinfunction "DEC4_9") (pintype "power_in"))
    )
    (net (code "54") (name "unconnected-(U2-P0.00{slash}XL1-Pad13)") (class "Default")
      (node (ref "U2") (pin "13") (pinfunction "P0.00/XL1_13") (pintype "bidirectional"))
    )
    (net (code "55") (name "unconnected-(U2-P0.01{slash}XL2-Pad14)") (class "Default")
      (node (ref "U2") (pin "14") (pinfunction "P0.01/XL2_14") (pintype "bidirectional"))
    )
    (net (code "56") (name "unconnected-(U2-P0.02{slash}AIN0-Pad15)") (class "Default")
      (node (ref "U2") (pin "15") (pinfunction "P0.02/AIN0_15") (pintype "bidirectional"))
    )
    (net (code "57") (name "unconnected-(U2-P0.03{slash}AIN1-Pad16)") (class "Default")
      (node (ref "U2") (pin "16") (pinfunction "P0.03/AIN1_16") (pintype "bidirectional"))
    )
    (net (code "58") (name "unconnected-(U2-P0.04{slash}AIN2-Pad17)") (class "Default")
      (node (ref "U2") (pin "17") (pinfunction "P0.04/AIN2_17") (pintype "bidirectional"))
    )
    (net (code "59") (name "unconnected-(U2-P0.05{slash}AIN3-Pad18)") (class "Default")
      (node (ref "U2") (pin "18") (pinfunction "P0.05/AIN3_18") (pintype "bidirectional"))
    )
    (net (code "60") (name "unconnected-(U2-P0.07-Pad20)") (class "Default")
      (node (ref "U2") (pin "20") (pinfunction "P0.07_20") (pintype "bidirectional"))
    )
    (net (code "61") (name "unconnected-(U2-P0.09{slash}NFC1-Pad22)") (class "Default")
      (node (ref "U2") (pin "22") (pinfunction "P0.09/NFC1_22") (pintype "bidirectional"))
    )
    (net (code "62") (name "unconnected-(U2-P0.10{slash}NFC2-Pad23)") (class "Default")
      (node (ref "U2") (pin "23") (pinfunction "P0.10/NFC2_23") (pintype "bidirectional"))
    )
    (net (code "63") (name "unconnected-(U2-P0.13-Pad27)") (class "Default")
      (node (ref "U2") (pin "27") (pinfunction "P0.13_27") (pintype "bidirectional"))
    )
    (net (code "64") (name "unconnected-(U2-P0.14{slash}TRACEDATA(3)-Pad28)") (class "Default")
      (node (ref "U2") (pin "28") (pinfunction "P0.14/TRACEDATA(3)_28") (pintype "bidirectional"))
    )
    (net (code "65") (name "unconnected-(U2-P0.15{slash}TRACEDATA(2)-Pad29)") (class "Default")
      (node (ref "U2") (pin "29") (pinfunction "P0.15/TRACEDATA(2)_29") (pintype "bidirectional"))
    )
    (net (code "66") (name "unconnected-(U2-P0.16{slash}TRACEDATA(1)-Pad30)") (class "Default")
      (node (ref "U2") (pin "30") (pinfunction "P0.16/TRACEDATA(1)_30") (pintype "bidirectional"))
    )
    (net (code "67") (name "unconnected-(U2-P0.23-Pad41)") (class "Default")
      (node (ref "U2") (pin "41") (pinfunction "P0.23_41") (pintype "bidirectional"))
    )
    (net (code "68") (name "unconnected-(U2-P0.24-Pad40)") (class "Default")
      (node (ref "U2") (pin "40") (pinfunction "P0.24_40") (pintype "bidirectional"))
    )
    (net (code "69") (name "unconnected-(U2-P0.28{slash}AIN4-Pad5)") (class "Default")
      (node (ref "U2") (pin "5") (pinfunction "P0.28/AIN4_5") (pintype "bidirectional"))
    )
    (net (code "70") (name "unconnected-(U2-P0.29{slash}AIN5-Pad6)") (class "Default")
      (node (ref "U2") (pin "6") (pinfunction "P0.29/AIN5_6") (pintype "bidirectional"))
    )
    (net (code "71") (name "unconnected-(U2-P0.30AIN6-Pad7)") (class "Default")
      (node (ref "U2") (pin "7") (pinfunction "P0.30AIN6_7") (pintype "bidirectional"))
    )
    (net (code "72") (name "unconnected-(U4-CTS-Pad18)") (class "Default")
      (node (ref "U4") (pin "18") (pinfunction "CTS_18") (pintype "input+no_connect"))
    )
    (net (code "73") (name "unconnected-(U4-DCD-Pad24)") (class "Default")
      (node (ref "U4") (pin "24") (pinfunction "DCD_24") (pintype "input+no_connect"))
    )
    (net (code "74") (name "unconnected-(U4-DSR-Pad22)") (class "Default")
      (node (ref "U4") (pin "22") (pinfunction "DSR_22") (pintype "input+no_connect"))
    )
    (net (code "75") (name "unconnected-(U4-GPIO.0-Pad14)") (class "Default")
      (node (ref "U4") (pin "14") (pinfunction "GPIO.0_14") (pintype "bidirectional+no_connect"))
    )
    (net (code "76") (name "unconnected-(U4-GPIO.1-Pad13)") (class "Default")
      (node (ref "U4") (pin "13") (pinfunction "GPIO.1_13") (pintype "bidirectional+no_connect"))
    )
    (net (code "77") (name "unconnected-(U4-GPIO.2-Pad12)") (class "Default")
      (node (ref "U4") (pin "12") (pinfunction "GPIO.2_12") (pintype "bidirectional+no_connect"))
    )
    (net (code "78") (name "unconnected-(U4-GPIO.3-Pad11)") (class "Default")
      (node (ref "U4") (pin "11") (pinfunction "GPIO.3_11") (pintype "bidirectional+no_connect"))
    )
    (net (code "79") (name "unconnected-(U4-NC-Pad10)") (class "Default")
      (node (ref "U4") (pin "10") (pinfunction "NC_10") (pintype "passive+no_connect"))
    )
    (net (code "80") (name "unconnected-(U4-RI-Pad1)") (class "Default")
      (node (ref "U4") (pin "1") (pinfunction "RI_1") (pintype "input+no_connect"))
    )
    (net (code "81") (name "unconnected-(U4-RSTn-Pad9)") (class "Default")
      (node (ref "U4") (pin "9") (pinfunction "RSTn_9") (pintype "bidirectional+no_connect"))
    )
    (net (code "82") (name "unconnected-(U4-RTS-Pad19)") (class "Default")
      (node (ref "U4") (pin "19") (pinfunction "RTS_19") (pintype "output+no_connect"))
    )
    (net (code "83") (name "unconnected-(U4-SUSPEND-Pad17)") (class "Default")
      (node (ref "U4") (pin "17") (pinfunction "SUSPEND_17") (pintype "output+no_connect"))
    )
    (net (code "84") (name "unconnected-(U4-SUSPENDn-Pad15)") (class "Default")
      (node (ref "U4") (pin "15") (pinfunction "SUSPENDn_15") (pintype "output+no_connect"))
    )
  )
)
